# SensorBoard.net
KiCad netlist of a schematic drawn in Altium Designer
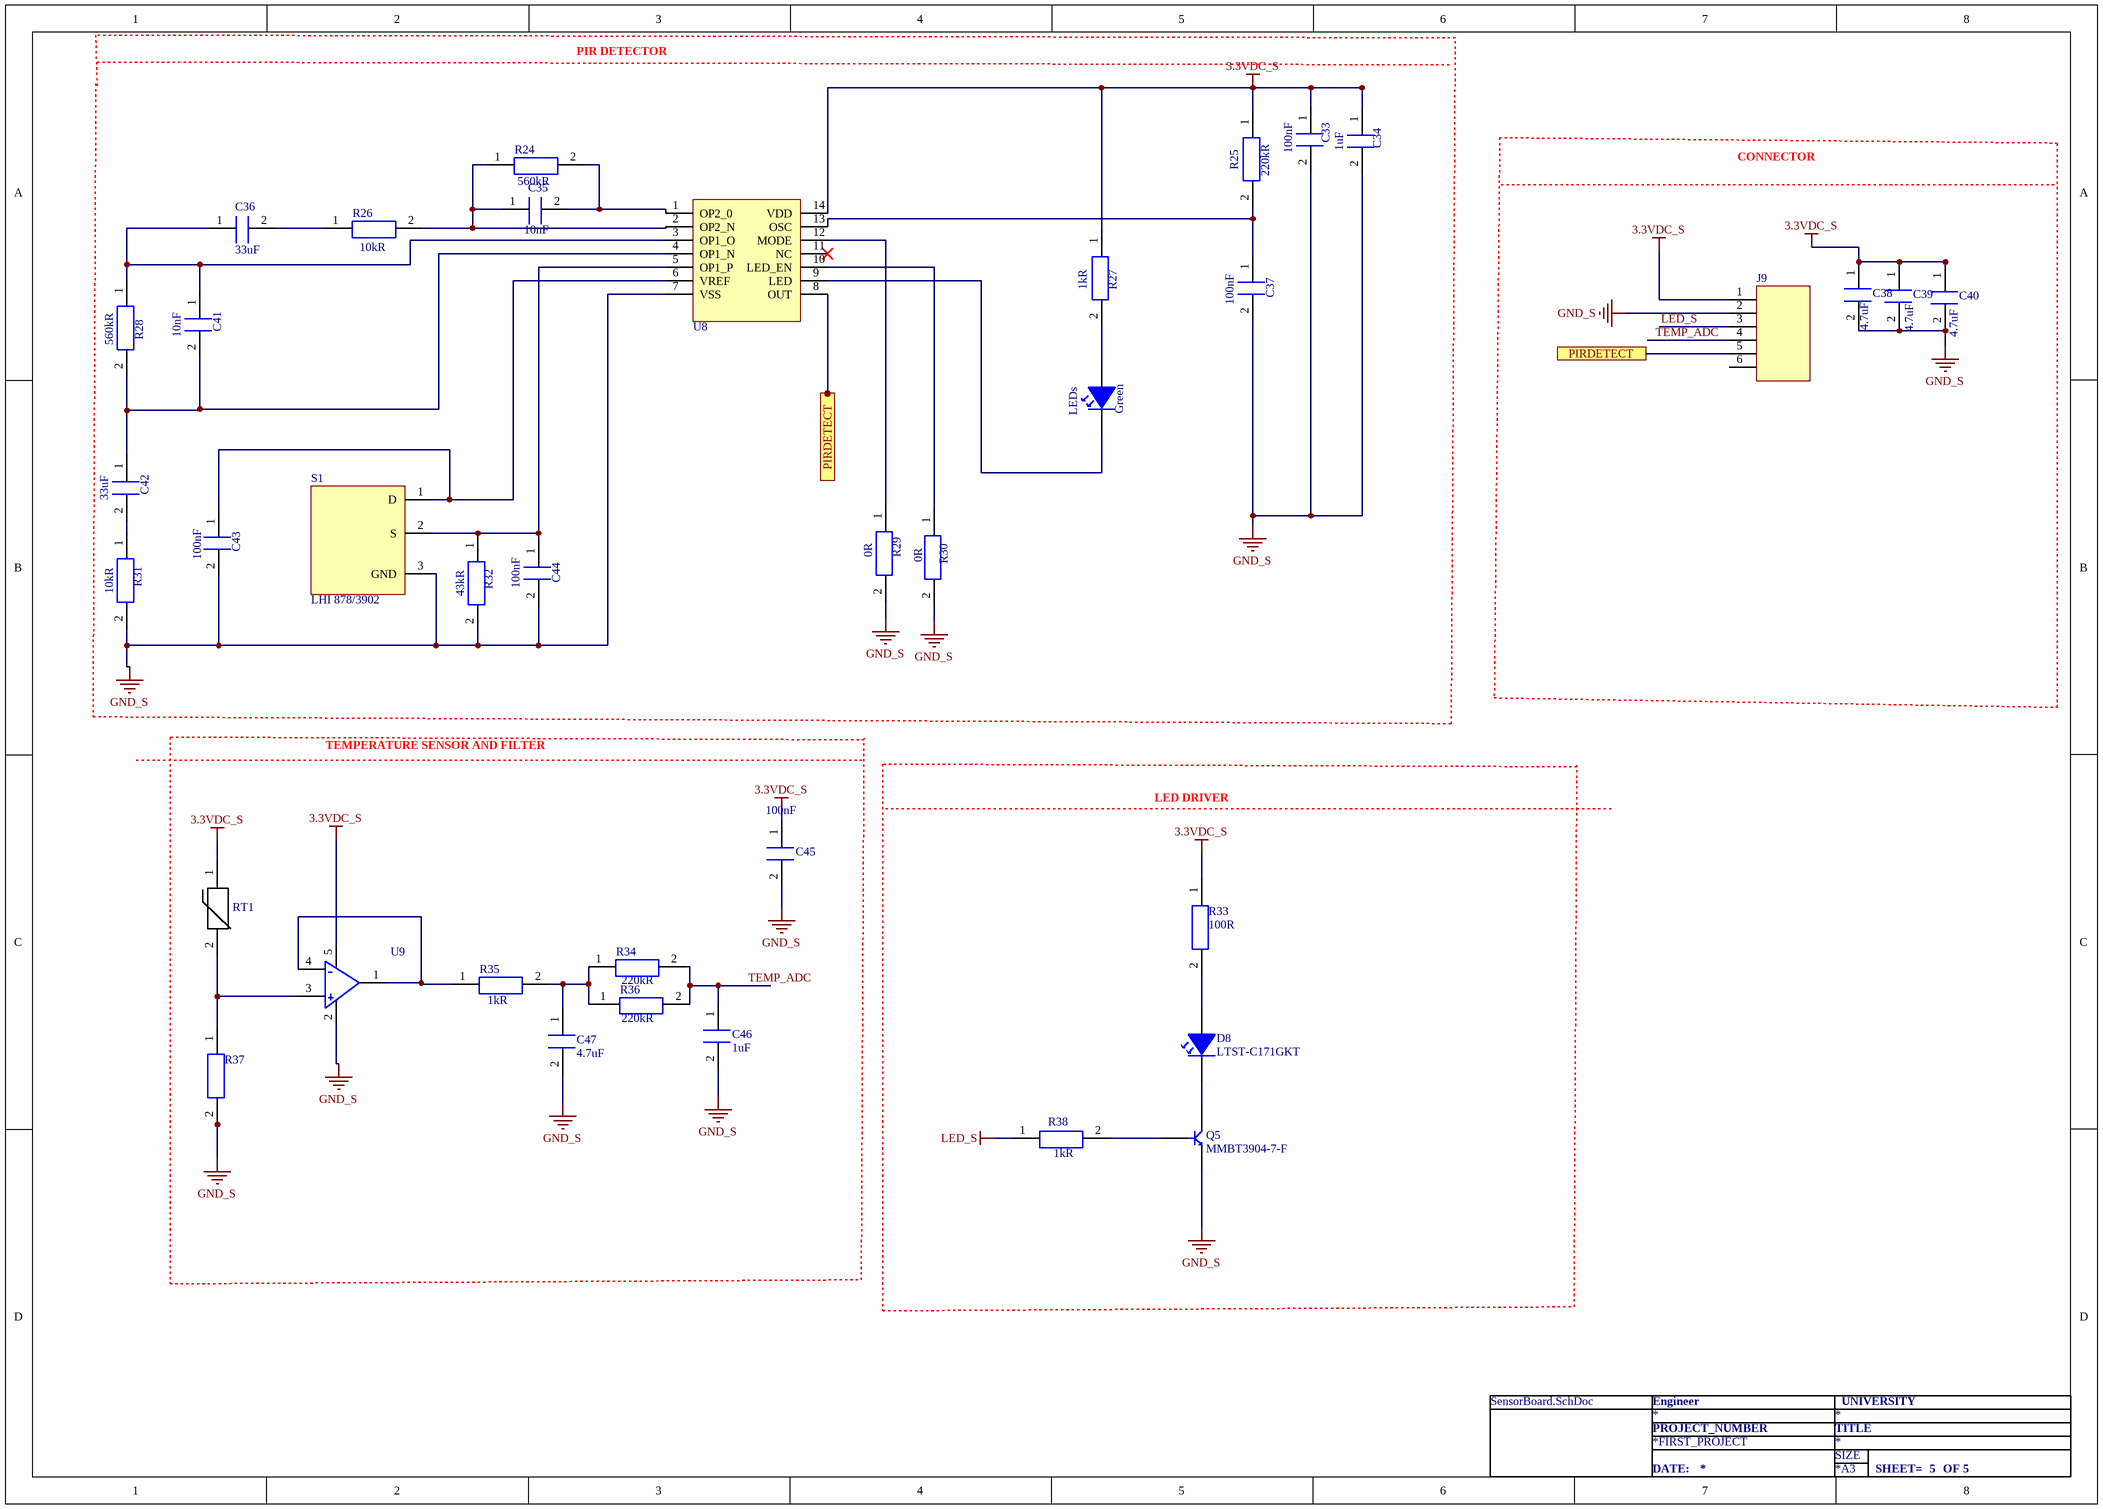
[diagram p0: SensorBoard.SchDoc]

(export (version "E")
  (design (tool "Eeschema 10.0.6"))
  (components
    (comp (ref "C33")
      (value "CAP CF 100NF 0805")
      (footprint "CAP_0805")
      (description "CAP CER 0.1UF 50V X7R 0805")
      (fields
        (field (name "MANUFACTURER") "Samsung")
        (field (name "MANUFACTURER PART NUMBER") "CL21B104KBCNNNC")
        (field (name "CAPACITANCE") "100nF")
      )
      (libsource (lib "first_project_library") (part "CAP CF 100NF 0805"))
    )
    (comp (ref "C34")
      (value "CAP CER 1UF 0805")
      (footprint "CAP_0805")
      (description "CAP CER 1UF 25V X5R 0805")
      (fields
        (field (name "MANUFACTURER") "Murata")
        (field (name "MANUFACTURER PART NUMBER") "GRM216R61E105KA12D")
        (field (name "CAPACITANCE") "1uF")
      )
      (libsource (lib "first_project_library") (part "CAP CER 1UF 0805"))
    )
    (comp (ref "C35")
      (value "CAP CER 10nF 0603")
      (footprint "CAP_0603")
      (description "Multilayer Ceramic Capacitor, 0.01 F, 10%, X7R, 16 V, 0603 [1608 Metric] RoHS Compliant: Yes")
      (fields
        (field (name "MANUFACTURER") "Walsin Technologies")
        (field (name "MANUFACTURER PART NUMBER") "0603B103K160CT")
        (field (name "CAPACITANCE") "10nF")
      )
      (libsource (lib "first_project_library") (part "CAP CER 10nF 0603"))
    )
    (comp (ref "C36")
      (value "C3216X5R1E336M160AC")
      (footprint "CAP_1206")
      (description "C Series 1206 33 uF 25 V ±20 % Tolerance X5R SMT Multilayer Ceramic Capacitor")
      (fields
        (field (name "MANUFACTURER") "TDK")
        (field (name "TOLERANCE") "20%")
        (field (name "CAPACITANCE") "33uF")
        (field (name "THIS PART IS DESIGNED") "alperen")
      )
      (libsource (lib "first_project_library") (part "CAP CER 33uF 1206"))
    )
    (comp (ref "C37")
      (value "CAP CF 100NF 0805")
      (footprint "CAP_0805")
      (description "CAP CER 0.1UF 50V X7R 0805")
      (fields
        (field (name "MANUFACTURER") "Samsung")
        (field (name "MANUFACTURER PART NUMBER") "CL21B104KBCNNNC")
        (field (name "CAPACITANCE") "100nF")
      )
      (libsource (lib "first_project_library") (part "CAP CF 100NF 0805"))
    )
    (comp (ref "C38")
      (value "CAP CER 4.7uF 0805")
      (footprint "CAP_0805")
      (description "CAP CER 4.7UF 25V X5R 0805")
      (fields
        (field (name "MANUFACTURER") "Samsung")
        (field (name "MANUFACTURER PART NUMBER") "CL21A475KAQNNNE")
        (field (name "CAPACITANCE") "4.7uF")
      )
      (libsource (lib "first_project_library") (part "CAP CER 4.7uF 0805"))
    )
    (comp (ref "C39")
      (value "CAP CER 4.7uF 0805")
      (footprint "CAP_0805")
      (description "CAP CER 4.7UF 25V X5R 0805")
      (fields
        (field (name "MANUFACTURER") "Samsung")
        (field (name "MANUFACTURER PART NUMBER") "CL21A475KAQNNNE")
        (field (name "CAPACITANCE") "4.7uF")
      )
      (libsource (lib "first_project_library") (part "CAP CER 4.7uF 0805"))
    )
    (comp (ref "C40")
      (value "CAP CER 4.7uF 0805")
      (footprint "CAP_0805")
      (description "CAP CER 4.7UF 25V X5R 0805")
      (fields
        (field (name "MANUFACTURER") "Samsung")
        (field (name "MANUFACTURER PART NUMBER") "CL21A475KAQNNNE")
        (field (name "CAPACITANCE") "4.7uF")
      )
      (libsource (lib "first_project_library") (part "CAP CER 4.7uF 0805"))
    )
    (comp (ref "C41")
      (value "CAP CER 10nF 0603")
      (footprint "CAP_0603")
      (description "Multilayer Ceramic Capacitor, 0.01 F, 10%, X7R, 16 V, 0603 [1608 Metric] RoHS Compliant: Yes")
      (fields
        (field (name "MANUFACTURER") "Walsin Technologies")
        (field (name "MANUFACTURER PART NUMBER") "0603B103K160CT")
        (field (name "CAPACITANCE") "10nF")
      )
      (libsource (lib "first_project_library") (part "CAP CER 10nF 0603"))
    )
    (comp (ref "C42")
      (value "C3216X5R1E336M160AC")
      (footprint "CAP_1206")
      (description "C Series 1206 33 uF 25 V ±20 % Tolerance X5R SMT Multilayer Ceramic Capacitor")
      (fields
        (field (name "MANUFACTURER") "TDK")
        (field (name "TOLERANCE") "20%")
        (field (name "CAPACITANCE") "33uF")
        (field (name "THIS PART IS DESIGNED") "alperen")
      )
      (libsource (lib "first_project_library") (part "CAP CER 33uF 1206"))
    )
    (comp (ref "C43")
      (value "CAP CF 100NF 0805")
      (footprint "CAP_0805")
      (description "CAP CER 0.1UF 50V X7R 0805")
      (fields
        (field (name "MANUFACTURER") "Samsung")
        (field (name "MANUFACTURER PART NUMBER") "CL21B104KBCNNNC")
        (field (name "CAPACITANCE") "100nF")
      )
      (libsource (lib "first_project_library") (part "CAP CF 100NF 0805"))
    )
    (comp (ref "C44")
      (value "CAP CF 100NF 0805")
      (footprint "CAP_0805")
      (description "CAP CER 0.1UF 50V X7R 0805")
      (fields
        (field (name "MANUFACTURER") "Samsung")
        (field (name "MANUFACTURER PART NUMBER") "CL21B104KBCNNNC")
        (field (name "CAPACITANCE") "100nF")
      )
      (libsource (lib "first_project_library") (part "CAP CF 100NF 0805"))
    )
    (comp (ref "C45")
      (value "CAP CER 100nF 0603")
      (footprint "CAP_0603")
      (description "Multilayer Ceramic Capacitor, 0.1 uF, 10 V, ± 10%, X5R, 0402 [1005 Metric] %10")
      (fields
        (field (name "MANUFACTURER") "KEMET")
        (field (name "MANUFACTURER PART NUMBER") "C0402C104K8PACTU")
        (field (name "CAPACITANCE") "100nF")
      )
      (libsource (lib "first_project_library") (part "CAP CER 100nF 0603"))
    )
    (comp (ref "C46")
      (value "CAP CER 1UF 0805")
      (footprint "CAP_0805")
      (description "CAP CER 1UF 25V X5R 0805")
      (fields
        (field (name "MANUFACTURER") "Murata")
        (field (name "MANUFACTURER PART NUMBER") "GRM216R61E105KA12D")
        (field (name "CAPACITANCE") "1uF")
      )
      (libsource (lib "first_project_library") (part "CAP CER 1UF 0805"))
    )
    (comp (ref "C47")
      (value "CAP CER 4.7uF 0805")
      (footprint "CAP_0805")
      (description "CAP CER 4.7UF 25V X5R 0805")
      (fields
        (field (name "MANUFACTURER") "Samsung")
        (field (name "MANUFACTURER PART NUMBER") "CL21A475KAQNNNE")
        (field (name "CAPACITANCE") "4.7uF")
      )
      (libsource (lib "first_project_library") (part "CAP CER 4.7uF 0805"))
    )
    (comp (ref "D7")
      (value "LTST-C171GKT")
      (footprint "LED_GREEN_0805 -")
      (description "Green 569nm LED Indication - Discrete 2.1V 0805 (2012 Metric)")
      (fields
        (field (name "MANUFACTURER") "Vishay Lite-On")
        (field (name "CATEGORY") "LEDs")
        (field (name "COLOR") "Green")
        (field (name "THIS PART IS DESIGNED") "alperen")
      )
      (libsource (lib "first_project_library") (part "LED_GREEN_0805"))
    )
    (comp (ref "D8")
      (value "LTST-C171GKT")
      (footprint "LED_GREEN_0805 -")
      (description "Green 569nm LED Indication - Discrete 2.1V 0805 (2012 Metric)")
      (fields (field (name "MANUFACTURER") "Vishay Lite-On") (field (name "THIS PART IS DESIGNED") "alperen"))
      (libsource (lib "first_project_library") (part "LED_GREEN_0805"))
    )
    (comp (ref "J9")
      (value "64800611622")
      (footprint "64800611622")
      (description "Conn, Header, 6POS, 1ROW, 1.5MM;")
      (fields
        (field (name "MANUFACTURER") "Wurth Electronics")
        (field (name "THIS PART IS DESIGNED") "alperen")
      )
      (libsource (lib "first_project_library") (part "64800611622_CONN_6PİN"))
    )
    (comp (ref "Q5")
      (value "MMBT3904-7-F")
      (footprint "SOT-23F")
      (description "NPN Ic=200mA Vceo=40V hfe=100~300 fT=310MHz P=300mW SOT-23")
      (fields (field (name "MANUFACTURER") "Diodes Zetex") (field (name "THIS PART IS DESIGNED") "alperen"))
      (libsource (lib "first_project_library") (part "MMBT3904-7-F"))
    )
    (comp (ref "R24")
      (value "RC0402JR-0710KL")
      (footprint "RES_0603")
      (description "Res Thick Film 0603 560K Ohm 1% 0.1W(1/10W) ±100ppm/C Pad SMD T/R")
      (fields
        (field (name "MANUFACTURER") "Yageo")
        (field (name "TOLERANCE") "5%")
        (field (name "RESISTANCE") "560kR")
        (field (name "THIS PART IS DESIGNED") "alperen")
      )
      (libsource (lib "") (part "RES 560K 0603_1"))
    )
    (comp (ref "R25")
      (value "RC0603JR-07220KL")
      (footprint "RES_0603")
      (description "Res Thick Film 0603 220K Ohm 5% 0.1W(1/10W) ±100ppm/C Pad SMD T/R")
      (fields
        (field (name "MANUFACTURER") "Yageo")
        (field (name "TOLERANCE") "5%")
        (field (name "RESISTANCE") "220kR")
        (field (name "THIS PART IS DESIGNED") "alperen")
      )
      (libsource (lib "first_project_library") (part "RES 220K 0603"))
    )
    (comp (ref "R26")
      (value "RES 10KOHM%1 0603")
      (footprint "RES_0603")
      (description "RES SMD 10K OHM 1% 1/10W 0603")
      (fields
        (field (name "MANUFACTURER") "Yageo")
        (field (name "MANUFACTURER PART NUMBER") "RC0603FR-0710KL")
        (field (name "RESISTANCE") "10kR")
      )
      (libsource (lib "") (part "RES 10KOHM 0603_1"))
    )
    (comp (ref "R27")
      (value "RES_1KOHM")
      (footprint "RES_0603")
      (description "Res Thin Film 0603 1K Ohm 0.1% 1/10W ±25ppm/°C Molded SMD SMD Punched Carrier T/R")
      (fields
        (field (name "MANUFACTURER") "Panasonic")
        (field (name "MANUFACTURER PART NUMBER") "ERA-3AEB102V")
        (field (name "RESISTANCE") "1kR")
        (field (name "THIS PART IS DESIGNED") "alperen")
      )
      (libsource (lib "") (part "RES_1KOHM_1"))
    )
    (comp (ref "R28")
      (value "RC0402JR-0710KL")
      (footprint "RES_0603")
      (description "Res Thick Film 0603 560K Ohm 1% 0.1W(1/10W) ±100ppm/C Pad SMD T/R")
      (fields
        (field (name "MANUFACTURER") "Yageo")
        (field (name "TOLERANCE") "5%")
        (field (name "RESISTANCE") "560kR")
        (field (name "THIS PART IS DESIGNED") "alperen")
      )
      (libsource (lib "first_project_library") (part "RES 560K 0603"))
    )
    (comp (ref "R29")
      (value "RES 0OHM 0603")
      (footprint "RES_0603")
      (description "RES SMD 0 OHM JUMPER 1/10W 0603")
      (fields
        (field (name "MANUFACTURER") "Yageo")
        (field (name "MANUFACTURER PART NUMBER") "RC0603JR-070RL")
        (field (name "RESISTANCE") "0R")
      )
      (libsource (lib "first_project_library") (part "RES 0OHM 0603"))
    )
    (comp (ref "R30")
      (value "RES 0OHM 0603")
      (footprint "RES_0603")
      (description "RES SMD 0 OHM JUMPER 1/10W 0603")
      (fields
        (field (name "MANUFACTURER") "Yageo")
        (field (name "MANUFACTURER PART NUMBER") "RC0603JR-070RL")
        (field (name "RESISTANCE") "0R")
      )
      (libsource (lib "first_project_library") (part "RES 0OHM 0603"))
    )
    (comp (ref "R31")
      (value "RES 10KOHM%1 0603")
      (footprint "RES_0603")
      (description "RES SMD 10K OHM 1% 1/10W 0603")
      (fields
        (field (name "MANUFACTURER") "Yageo")
        (field (name "MANUFACTURER PART NUMBER") "RC0603FR-0710KL")
        (field (name "RESISTANCE") "10kR")
      )
      (libsource (lib "first_project_library") (part "RES 10KOHM 0603"))
    )
    (comp (ref "R32")
      (value "RC0603JR-0743KL")
      (footprint "RES_0603")
      (description "Res Thick Film 0603 43K Ohm 5% 0.1W(1/10W) ±100ppm/°C Pad SMD T/R")
      (fields
        (field (name "MANUFACTURER") "Yageo")
        (field (name "TOLERANCE") "5%")
        (field (name "RESISTANCE") "43kR")
        (field (name "THIS PART IS DESIGNED") "alperen")
      )
      (libsource (lib "first_project_library") (part "RES 43K 0603"))
    )
    (comp (ref "R33")
      (value "RES_100OHM_0603")
      (footprint "RES_0603")
      (description "Res Thick Film 0603 100 Ohm 1% 1/10W ±100ppm/°C Molded SMD Paper T/R")
      (fields
        (field (name "MANUFACTURER") "Vishay Dale")
        (field (name "MANUFACTURER PART NUMBER") "CRCW0603100RFKEA")
        (field (name "RESISTANCE") "100R")
      )
      (libsource (lib "first_project_library") (part "RES_100OHM_0603"))
    )
    (comp (ref "R34")
      (value "RC0603JR-07220KL")
      (footprint "RES_0603")
      (description "Res Thick Film 0603 220K Ohm 5% 0.1W(1/10W) ±100ppm/C Pad SMD T/R")
      (fields
        (field (name "MANUFACTURER") "Yageo")
        (field (name "TOLERANCE") "5%")
        (field (name "RESISTANCE") "220kR")
        (field (name "THIS PART IS DESIGNED") "alperen")
      )
      (libsource (lib "") (part "RES 220K 0603_1"))
    )
    (comp (ref "R35")
      (value "RES_1KOHM")
      (footprint "RES_0603")
      (description "Res Thin Film 0603 1K Ohm 0.1% 1/10W ±25ppm/°C Molded SMD SMD Punched Carrier T/R")
      (fields
        (field (name "MANUFACTURER") "Panasonic")
        (field (name "MANUFACTURER PART NUMBER") "ERA-3AEB102V")
        (field (name "RESISTANCE") "1kR")
        (field (name "THIS PART IS DESIGNED") "alperen")
      )
      (libsource (lib "first_project_library") (part "RES_1KOHM"))
    )
    (comp (ref "R36")
      (value "RC0603JR-07220KL")
      (footprint "RES_0603")
      (description "Res Thick Film 0603 220K Ohm 5% 0.1W(1/10W) ±100ppm/C Pad SMD T/R")
      (fields
        (field (name "MANUFACTURER") "Yageo")
        (field (name "TOLERANCE") "5%")
        (field (name "RESISTANCE") "220kR")
        (field (name "THIS PART IS DESIGNED") "alperen")
      )
      (libsource (lib "") (part "RES 220K 0603_1"))
    )
    (comp (ref "R37")
      (value "RES 10KOHM%1 0603")
      (footprint "RES_0603")
      (description "RES SMD 10K OHM 1% 1/10W 0603")
      (fields
        (field (name "MANUFACTURER") "Yageo")
        (field (name "MANUFACTURER PART NUMBER") "RC0603FR-0710KL")
      )
      (libsource (lib "first_project_library") (part "RES 10KOHM 0603"))
    )
    (comp (ref "R38")
      (value "RES_1KOHM")
      (footprint "RES_0603")
      (description "Res Thin Film 0603 1K Ohm 0.1% 1/10W ±25ppm/°C Molded SMD SMD Punched Carrier T/R")
      (fields
        (field (name "MANUFACTURER") "Panasonic")
        (field (name "MANUFACTURER PART NUMBER") "ERA-3AEB102V")
        (field (name "RESISTANCE") "1kR")
        (field (name "THIS PART IS DESIGNED") "alperen")
      )
      (libsource (lib "first_project_library") (part "RES_1KOHM"))
    )
    (comp (ref "RT1")
      (value "TFPT1206L1002FM")
      (footprint "RES_1206")
      (description "Thermistor PTC 10K Ohm 1% 2-Pin 1206 Surface Mount Solder Pad T/R Automotive")
      (fields
        (field (name "MANUFACTURER") "Vishay Dale")
        (field (name "MANUFACTURER PART NUMBER") "TFPT1206L1002FV")
      )
      (libsource (lib "first_project_library") (part "TFPT1206L1002FM"))
    )
    (comp (ref "S1")
      (value "LHI 878/3902")
      (footprint "LHI 878/3902")
      (description "Sensor PIR (Passive Infrared) TO-205AA, TO-5-3 Metal Can")
      (fields
        (field (name "MANUFACTURER") "Excelitas")
        (field (name "MANUFACTURER PART NUMBER") "LHI878/3902")
      )
      (libsource (lib "first_project_library") (part "LHI 878/3902"))
    )
    (comp (ref "U8")
      (value "NCS36000DRG")
      (footprint "SOIC14")
      (description "NCS36000 Series Single 5.75V Passive Infrared Detector Controller (PIR) -SOIC-14")
      (fields
        (field (name "MANUFACTURER") "ON Semiconductor")
        (field (name "THIS PART IS DESIGNED") "alperen")
      )
      (libsource (lib "first_project_library") (part "NCS36000"))
    )
    (comp (ref "U9")
      (value "OPA314AIDBVR")
      (footprint "SOT23_5")
      (description "IC OPAMP GP 3MHZ RRO SOT23-5")
      (fields
        (field (name "MANUFACTURER") "Texas Instruments")
        (field (name "THIS PART IS DESIGNED") "alperen")
      )
      (libsource (lib "first_project_library") (part "OPA 314"))
    )
  )
  (nets
    (net (code "1") (name "/PIRDETECT") (class "Default")
      (node (ref "J9") (pin "5") (pinfunction "GND_5") (pintype "passive"))
      (node (ref "U8") (pin "8") (pinfunction "OUT_8") (pintype "passive"))
    )
    (net (code "2") (name "/TEMP_ADC") (class "Default")
      (node (ref "C46") (pin "1") (pintype "passive"))
      (node (ref "J9") (pin "4") (pinfunction "NC_4") (pintype "passive"))
      (node (ref "R34") (pin "2") (pintype "passive"))
      (node (ref "R36") (pin "2") (pintype "passive"))
    )
    (net (code "3") (name "3.3VDC_S") (class "Default")
      (node (ref "C33") (pin "1") (pintype "passive"))
      (node (ref "C34") (pin "1") (pintype "passive"))
      (node (ref "C38") (pin "1") (pintype "passive"))
      (node (ref "C39") (pin "1") (pintype "passive"))
      (node (ref "C40") (pin "1") (pintype "passive"))
      (node (ref "C45") (pin "1") (pintype "passive"))
      (node (ref "J9") (pin "1") (pinfunction "VCC_1") (pintype "passive"))
      (node (ref "R25") (pin "1") (pintype "passive"))
      (node (ref "R27") (pin "1") (pintype "passive"))
      (node (ref "R33") (pin "1") (pintype "passive"))
      (node (ref "RT1") (pin "1") (pintype "passive"))
      (node (ref "U8") (pin "14") (pinfunction "VDD_14") (pintype "passive"))
      (node (ref "U9") (pin "5") (pintype "passive"))
    )
    (net (code "4") (name "GND_S") (class "Default")
      (node (ref "C33") (pin "2") (pintype "passive"))
      (node (ref "C34") (pin "2") (pintype "passive"))
      (node (ref "C37") (pin "2") (pintype "passive"))
      (node (ref "C38") (pin "2") (pintype "passive"))
      (node (ref "C39") (pin "2") (pintype "passive"))
      (node (ref "C40") (pin "2") (pintype "passive"))
      (node (ref "C43") (pin "2") (pintype "passive"))
      (node (ref "C44") (pin "2") (pintype "passive"))
      (node (ref "C45") (pin "2") (pintype "passive"))
      (node (ref "C46") (pin "2") (pintype "passive"))
      (node (ref "C47") (pin "2") (pintype "passive"))
      (node (ref "J9") (pin "2") (pinfunction "RX_2") (pintype "passive"))
      (node (ref "Q5") (pin "2") (pinfunction "E_2") (pintype "passive"))
      (node (ref "R29") (pin "2") (pintype "passive"))
      (node (ref "R30") (pin "2") (pintype "passive"))
      (node (ref "R31") (pin "2") (pintype "passive"))
      (node (ref "R32") (pin "2") (pintype "passive"))
      (node (ref "R37") (pin "2") (pintype "passive"))
      (node (ref "S1") (pin "3") (pinfunction "GND_3") (pintype "passive"))
      (node (ref "U8") (pin "7") (pinfunction "VSS_7") (pintype "passive"))
      (node (ref "U9") (pin "2") (pintype "passive"))
    )
    (net (code "5") (name "LED_S") (class "Default")
      (node (ref "J9") (pin "3") (pinfunction "TX_3") (pintype "passive"))
      (node (ref "R38") (pin "1") (pintype "passive"))
    )
    (net (code "6") (name "Net-(C36-Pad2)") (class "Default")
      (node (ref "C36") (pin "2") (pintype "passive"))
      (node (ref "R26") (pin "1") (pintype "passive"))
    )
    (net (code "7") (name "Net-(C42-Pad2)") (class "Default")
      (node (ref "C42") (pin "2") (pintype "passive"))
      (node (ref "R31") (pin "1") (pintype "passive"))
    )
    (net (code "8") (name "Net-(C47-Pad1)") (class "Default")
      (node (ref "C47") (pin "1") (pintype "passive"))
      (node (ref "R34") (pin "1") (pintype "passive"))
      (node (ref "R35") (pin "2") (pintype "passive"))
      (node (ref "R36") (pin "1") (pintype "passive"))
    )
    (net (code "9") (name "Net-(D7-Pad2)") (class "Default")
      (node (ref "D7") (pin "2") (pinfunction "2_2") (pintype "passive"))
      (node (ref "R27") (pin "2") (pintype "passive"))
    )
    (net (code "10") (name "Net-(D8-Pad2)") (class "Default")
      (node (ref "D8") (pin "2") (pinfunction "2_2") (pintype "passive"))
      (node (ref "R33") (pin "2") (pintype "passive"))
    )
    (net (code "11") (name "Net-(Q5-B)") (class "Default")
      (node (ref "Q5") (pin "1") (pinfunction "B_1") (pintype "passive"))
      (node (ref "R38") (pin "2") (pintype "passive"))
    )
    (net (code "12") (name "Net-(Q5-C)") (class "Default")
      (node (ref "D8") (pin "1") (pintype "passive"))
      (node (ref "Q5") (pin "3") (pinfunction "C_3") (pintype "passive"))
    )
    (net (code "13") (name "Net-(R35-Pad1)") (class "Default")
      (node (ref "R35") (pin "1") (pintype "passive"))
      (node (ref "U9") (pin "1") (pintype "passive"))
      (node (ref "U9") (pin "4") (pintype "passive"))
    )
    (net (code "14") (name "Net-(R37-Pad1)") (class "Default")
      (node (ref "R37") (pin "1") (pintype "passive"))
      (node (ref "RT1") (pin "2") (pintype "passive"))
      (node (ref "U9") (pin "3") (pintype "passive"))
    )
    (net (code "15") (name "Net-(S1-D)") (class "Default")
      (node (ref "C43") (pin "1") (pintype "passive"))
      (node (ref "S1") (pin "1") (pinfunction "D_1") (pintype "passive"))
      (node (ref "U8") (pin "6") (pinfunction "VREF_6") (pintype "passive"))
    )
    (net (code "16") (name "Net-(S1-S)") (class "Default")
      (node (ref "C44") (pin "1") (pintype "passive"))
      (node (ref "R32") (pin "1") (pintype "passive"))
      (node (ref "S1") (pin "2") (pinfunction "S_2") (pintype "passive"))
      (node (ref "U8") (pin "5") (pinfunction "OP1_P_5") (pintype "passive"))
    )
    (net (code "17") (name "Net-(U8-LED)") (class "Default")
      (node (ref "D7") (pin "1") (pintype "passive"))
      (node (ref "U8") (pin "9") (pinfunction "LED_9") (pintype "passive"))
    )
    (net (code "18") (name "Net-(U8-LED_EN)") (class "Default")
      (node (ref "R30") (pin "1") (pintype "passive"))
      (node (ref "U8") (pin "10") (pinfunction "LED_EN_10") (pintype "passive"))
    )
    (net (code "19") (name "Net-(U8-MODE)") (class "Default")
      (node (ref "R29") (pin "1") (pintype "passive"))
      (node (ref "U8") (pin "12") (pinfunction "MODE_12") (pintype "passive"))
    )
    (net (code "20") (name "Net-(U8-OP1_N)") (class "Default")
      (node (ref "C41") (pin "2") (pintype "passive"))
      (node (ref "C42") (pin "1") (pintype "passive"))
      (node (ref "R28") (pin "2") (pintype "passive"))
      (node (ref "U8") (pin "4") (pinfunction "OP1_N_4") (pintype "passive"))
    )
    (net (code "21") (name "Net-(U8-OP1_O)") (class "Default")
      (node (ref "C36") (pin "1") (pintype "passive"))
      (node (ref "C41") (pin "1") (pintype "passive"))
      (node (ref "R28") (pin "1") (pintype "passive"))
      (node (ref "U8") (pin "3") (pinfunction "OP1_O_3") (pintype "passive"))
    )
    (net (code "22") (name "Net-(U8-OP2_0)") (class "Default")
      (node (ref "C35") (pin "2") (pintype "passive"))
      (node (ref "R24") (pin "2") (pintype "passive"))
      (node (ref "U8") (pin "1") (pinfunction "OP2_0_1") (pintype "passive"))
    )
    (net (code "23") (name "Net-(U8-OP2_N)") (class "Default")
      (node (ref "C35") (pin "1") (pintype "passive"))
      (node (ref "R24") (pin "1") (pintype "passive"))
      (node (ref "R26") (pin "2") (pintype "passive"))
      (node (ref "U8") (pin "2") (pinfunction "OP2_N_2") (pintype "passive"))
    )
    (net (code "24") (name "Net-(U8-OSC)") (class "Default")
      (node (ref "C37") (pin "1") (pintype "passive"))
      (node (ref "R25") (pin "2") (pintype "passive"))
      (node (ref "U8") (pin "13") (pinfunction "OSC_13") (pintype "passive"))
    )
    (net (code "25") (name "unconnected-(J9-GND-Pad6)") (class "Default")
      (node (ref "J9") (pin "6") (pinfunction "GND_6") (pintype "passive"))
    )
    (net (code "26") (name "unconnected-(U8-NC-Pad11)") (class "Default")
      (node (ref "U8") (pin "11") (pinfunction "NC_11") (pintype "passive+no_connect"))
    )
  )
)
